# FAT34p.net
KiCad netlist of a schematic drawn in Altium Designer
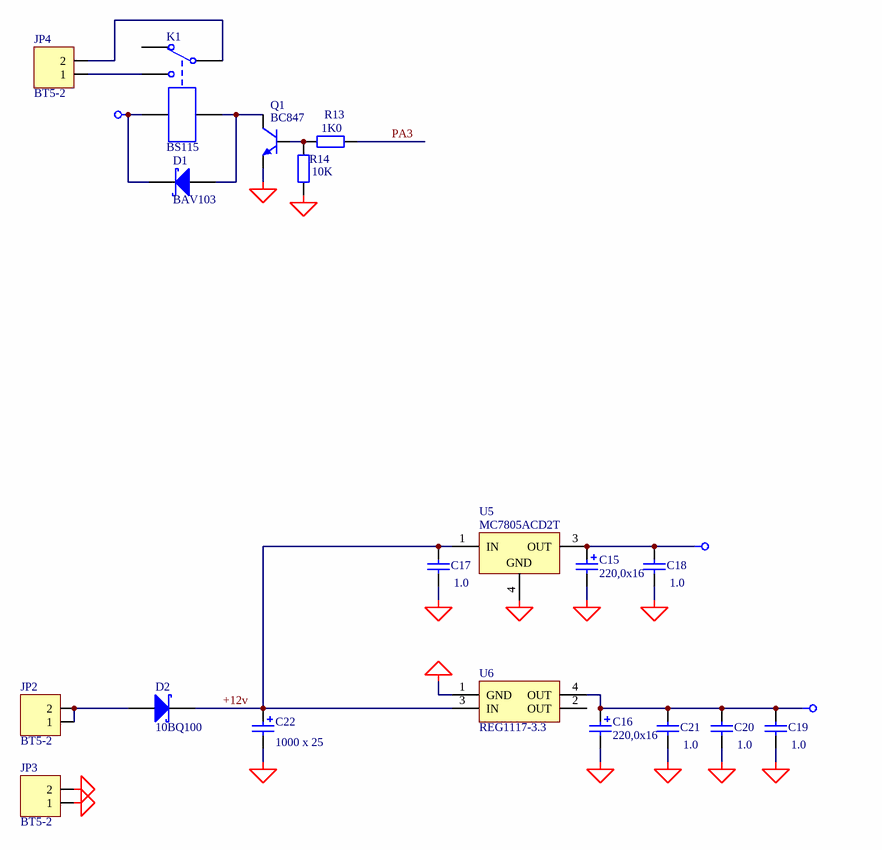
[diagram p0: FAT34p.SchDoc]

(export (version "E")
  (design (tool "Eeschema 10.0.6"))
  (components
    (comp (ref "C15")
      (value "220,0x16")
      (footprint "el3")
      (description "Polarized Capacitor (Radial)")
      (fields (field (name "MANUFACTURER") "Generic Components") (field (name "PUBLISHER") "Altium Limited"))
      (libsource (lib "BUF") (part "Cap Pol"))
    )
    (comp (ref "C16")
      (value "220,0x16")
      (footprint "el3")
      (description "Polarized Capacitor (Radial)")
      (fields (field (name "MANUFACTURER") "Generic Components") (field (name "PUBLISHER") "Altium Limited"))
      (libsource (lib "BUF") (part "Cap Pol"))
    )
    (comp (ref "C17")
      (value "1.0")
      (footprint "_1206")
      (description "Capacitor")
      (fields (field (name "MANUFACTURER") "Generic Components") (field (name "PUBLISHER") "Altium Limited"))
      (libsource (lib "BUF") (part "Cap"))
    )
    (comp (ref "C18")
      (value "1.0")
      (footprint "_1206")
      (description "Capacitor")
      (fields (field (name "MANUFACTURER") "Generic Components") (field (name "PUBLISHER") "Altium Limited"))
      (libsource (lib "BUF") (part "Cap"))
    )
    (comp (ref "C19")
      (value "1.0")
      (footprint "_1206")
      (description "Capacitor")
      (fields (field (name "MANUFACTURER") "Generic Components") (field (name "PUBLISHER") "Altium Limited"))
      (libsource (lib "BUF") (part "Cap"))
    )
    (comp (ref "C20")
      (value "1.0")
      (footprint "_1206")
      (description "Capacitor")
      (fields (field (name "MANUFACTURER") "Generic Components") (field (name "PUBLISHER") "Altium Limited"))
      (libsource (lib "BUF") (part "Cap"))
    )
    (comp (ref "C21")
      (value "1.0")
      (footprint "_1206")
      (description "Capacitor")
      (fields (field (name "MANUFACTURER") "Generic Components") (field (name "PUBLISHER") "Altium Limited"))
      (libsource (lib "BUF") (part "Cap"))
    )
    (comp (ref "C22")
      (value "1000 x 25")
      (footprint "el5")
      (description "Polarized Capacitor (Radial)")
      (fields (field (name "MANUFACTURER") "Generic Components") (field (name "PUBLISHER") "Altium Limited"))
      (libsource (lib "BUF") (part "Cap Pol1"))
    )
    (comp (ref "D1")
      (value "BAV103")
      (footprint "_1206d")
      (description "Schottky Rectifier")
      (fields
        (field (name "MANUFACTURER") "International Rectifier")
        (field (name "PUBLISHER") "Altium Limited")
      )
      (libsource (lib "IR Discrete Diode") (part "10BQ015"))
    )
    (comp (ref "D2")
      (value "10BQ100")
      (footprint "D_6_3")
      (description "Schottky Rectifier")
      (fields
        (field (name "MANUFACTURER") "International Rectifier")
        (field (name "PUBLISHER") "Altium Limited")
      )
      (libsource (lib "IR Discrete Diode") (part "10BQ015"))
    )
    (comp (ref "JP2")
      (value "BT5-2")
      (footprint "BT5-2-1")
      (description "Header, 3-Pin")
      (fields (field (name "MANUFACTURER") "Generic Components") (field (name "PUBLISHER") "Altium Limited"))
      (libsource (lib "PAL") (part "BT5-2"))
    )
    (comp (ref "JP3")
      (value "BT5-2")
      (footprint "BT5-2-1")
      (description "Header, 3-Pin")
      (fields (field (name "MANUFACTURER") "Generic Components") (field (name "PUBLISHER") "Altium Limited"))
      (libsource (lib "PAL") (part "BT5-2"))
    )
    (comp (ref "JP4")
      (value "BT5-2")
      (footprint "BT5-2-1")
      (description "Header, 3-Pin")
      (fields (field (name "MANUFACTURER") "Generic Components") (field (name "PUBLISHER") "Altium Limited"))
      (libsource (lib "PAL") (part "BT5-2"))
    )
    (comp (ref "K1")
      (value "BS115")
      (footprint "BS115")
      (description "Single-Pole Dual-Throw Relay")
      (fields (field (name "MANUFACTURER") "Generic Components") (field (name "PUBLISHER") "Altium Limited"))
      (libsource (lib "PAL") (part "BS115"))
    )
    (comp (ref "Q1")
      (value "BC847")
      (footprint "SO-G3")
      (description "General Purpose Transistor NPN Silicon")
      (fields (field (name "MANUFACTURER") "Motorola") (field (name "PUBLISHER") "Altium Limited"))
      (libsource (lib "PAL") (part "BC847ALT1"))
    )
    (comp (ref "R13")
      (value "1K0")
      (footprint "_1206")
      (description "Resistor")
      (fields (field (name "MANUFACTURER") "Generic Components") (field (name "PUBLISHER") "Altium Limited"))
      (libsource (lib "") (part "Res2_1"))
    )
    (comp (ref "R14")
      (value "10K")
      (footprint "_1206")
      (description "Resistor")
      (fields (field (name "MANUFACTURER") "Generic Components") (field (name "PUBLISHER") "Altium Limited"))
      (libsource (lib "Miscellaneous Devices") (part "Res2"))
    )
    (comp (ref "U5")
      (value "MC7805ACD2T")
      (footprint "D2PAK")
      (description "Three-Terminal Positive Voltage Regulator")
      (fields (field (name "MANUFACTURER") "ON Semiconductor") (field (name "PUBLISHER") "Altium Limited"))
      (libsource (lib "ON Semi Power Mgt Voltage Regulator") (part "MC7805ACD2T"))
    )
    (comp (ref "U6")
      (value "REG1117-3.3")
      (footprint "SIP-G3/E13")
      (description "800mA and 1A Low Dropout Positive Regulator 2.85V, 3.3V, 5V, and Adjustable")
      (fields (field (name "MANUFACTURER") "Burr-Brown") (field (name "PUBLISHER") "Altium Limited"))
      (libsource (lib "BB Power Mgt Voltage Regulator") (part "REG1117-3.3"))
    )
  )
  (nets
    (net (code "1") (name "+3v3") (class "Default")
      (node (ref "C16") (pin "1") (pinfunction "1_1") (pintype "passive"))
      (node (ref "C19") (pin "2") (pinfunction "2_2") (pintype "passive"))
      (node (ref "C20") (pin "2") (pinfunction "2_2") (pintype "passive"))
      (node (ref "C21") (pin "2") (pinfunction "2_2") (pintype "passive"))
      (node (ref "U6") (pin "4") (pinfunction "OUT_4") (pintype "power_in"))
    )
    (net (code "2") (name "+5v") (class "Default")
      (node (ref "C15") (pin "1") (pinfunction "1_1") (pintype "passive"))
      (node (ref "C18") (pin "2") (pinfunction "2_2") (pintype "passive"))
      (node (ref "U5") (pin "3") (pinfunction "OUT_3") (pintype "power_in"))
    )
    (net (code "3") (name "+12v") (class "Default")
      (node (ref "C17") (pin "2") (pinfunction "2_2") (pintype "passive"))
      (node (ref "C22") (pin "1") (pinfunction "1_1") (pintype "passive"))
      (node (ref "D1") (pin "2") (pinfunction "K_2") (pintype "passive"))
      (node (ref "D2") (pin "2") (pinfunction "K_2") (pintype "passive"))
      (node (ref "K1") (pin "5") (pinfunction "5_5") (pintype "passive"))
      (node (ref "U5") (pin "1") (pinfunction "IN_1") (pintype "power_in"))
      (node (ref "U6") (pin "3") (pinfunction "IN_3") (pintype "power_in"))
    )
    (net (code "4") (name "/PA3") (class "Default")
      (node (ref "R13") (pin "2") (pinfunction "2_2") (pintype "passive"))
    )
    (net (code "5") (name "GND") (class "Default")
      (node (ref "C15") (pin "2") (pinfunction "2_2") (pintype "passive"))
      (node (ref "C16") (pin "2") (pinfunction "2_2") (pintype "passive"))
      (node (ref "C17") (pin "1") (pinfunction "1_1") (pintype "passive"))
      (node (ref "C18") (pin "1") (pinfunction "1_1") (pintype "passive"))
      (node (ref "C19") (pin "1") (pinfunction "1_1") (pintype "passive"))
      (node (ref "C20") (pin "1") (pinfunction "1_1") (pintype "passive"))
      (node (ref "C21") (pin "1") (pinfunction "1_1") (pintype "passive"))
      (node (ref "C22") (pin "2") (pinfunction "2_2") (pintype "passive"))
      (node (ref "JP3") (pin "1") (pinfunction "1_1") (pintype "passive"))
      (node (ref "JP3") (pin "2") (pinfunction "2_2") (pintype "passive"))
      (node (ref "Q1") (pin "2") (pinfunction "E_2") (pintype "passive"))
      (node (ref "R14") (pin "2") (pinfunction "2_2") (pintype "passive"))
      (node (ref "U5") (pin "4") (pinfunction "GND_4") (pintype "power_in"))
      (node (ref "U6") (pin "1") (pinfunction "GND_1") (pintype "power_in"))
    )
    (net (code "6") (name "Net-(D1-A)") (class "Default")
      (node (ref "D1") (pin "1") (pinfunction "A_1") (pintype "passive"))
      (node (ref "K1") (pin "4") (pinfunction "4_4") (pintype "passive"))
      (node (ref "Q1") (pin "3") (pinfunction "C_3") (pintype "passive"))
    )
    (net (code "7") (name "Net-(D2-A)") (class "Default")
      (node (ref "D2") (pin "1") (pinfunction "A_1") (pintype "passive"))
      (node (ref "JP2") (pin "1") (pinfunction "1_1") (pintype "passive"))
      (node (ref "JP2") (pin "2") (pinfunction "2_2") (pintype "passive"))
    )
    (net (code "8") (name "Net-(JP4-Pad1)") (class "Default")
      (node (ref "JP4") (pin "1") (pinfunction "1_1") (pintype "passive"))
      (node (ref "K1") (pin "3") (pinfunction "3_3") (pintype "passive"))
    )
    (net (code "9") (name "Net-(JP4-Pad2)") (class "Default")
      (node (ref "JP4") (pin "2") (pinfunction "2_2") (pintype "passive"))
      (node (ref "K1") (pin "1") (pinfunction "1_1") (pintype "passive"))
    )
    (net (code "10") (name "Net-(Q1-B)") (class "Default")
      (node (ref "Q1") (pin "1") (pinfunction "B_1") (pintype "passive"))
      (node (ref "R13") (pin "1") (pinfunction "1_1") (pintype "passive"))
      (node (ref "R14") (pin "1") (pinfunction "1_1") (pintype "passive"))
    )
    (net (code "11") (name "unconnected-(K1-Pad2)") (class "Default")
      (node (ref "K1") (pin "2") (pinfunction "2_2") (pintype "passive"))
    )
    (net (code "12") (name "unconnected-(U6-OUT-Pad2)") (class "Default")
      (node (ref "U6") (pin "2") (pinfunction "OUT_2") (pintype "power_in"))
    )
  )
)
